# POE_Injector.net
KiCad netlist of a schematic drawn in EAGLE
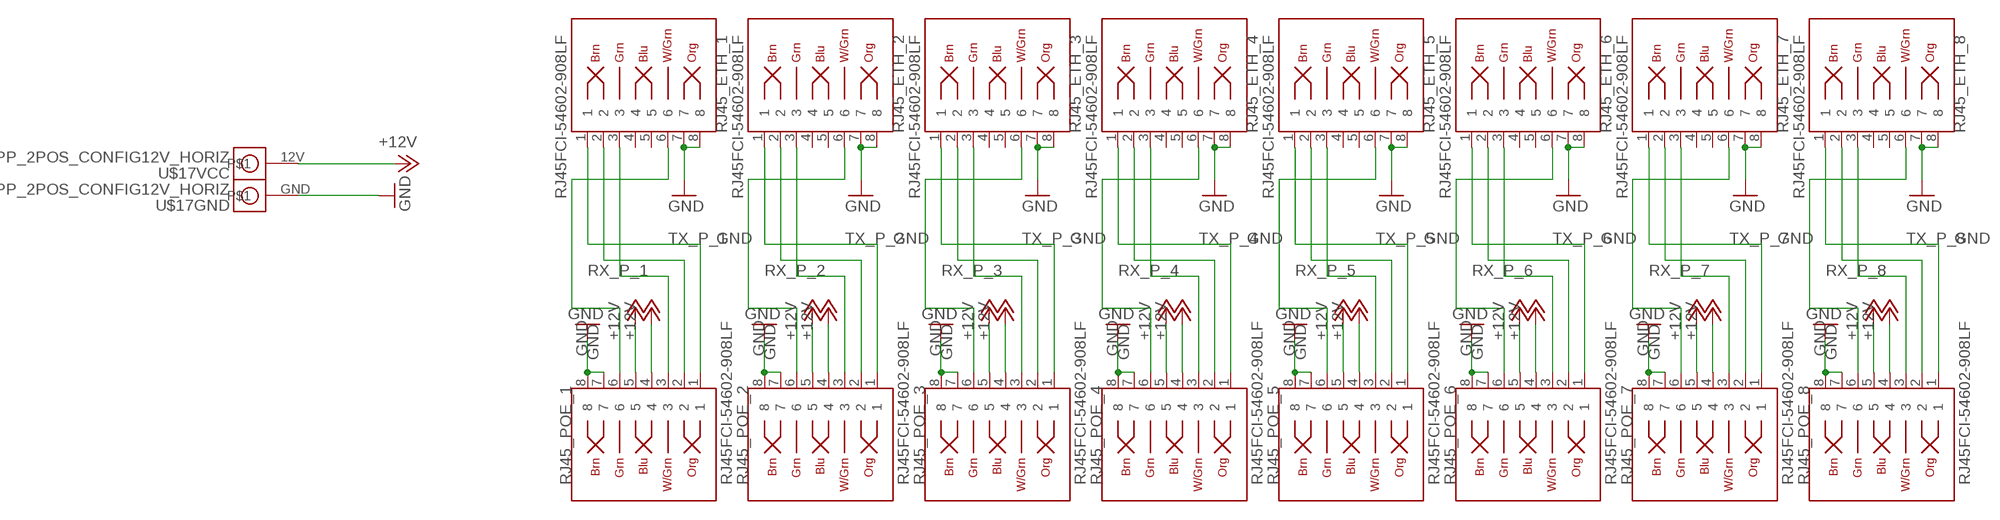
[diagram p0: schematic, sheet 1]

(export (version "E")
  (design (tool "Eeschema 10.0.6"))
  (components
    (comp (ref "RJ45_ETH_1")
      (value "RJ45FCI-54602-908LF")
      (footprint "eagle-import:FCI-54602-908LF")
      (libsource (lib "eagle-import") (part "RJ45FCI-54602-908LF"))
    )
    (comp (ref "RJ45_ETH_2")
      (value "RJ45FCI-54602-908LF")
      (footprint "eagle-import:FCI-54602-908LF")
      (libsource (lib "eagle-import") (part "RJ45FCI-54602-908LF"))
    )
    (comp (ref "RJ45_ETH_3")
      (value "RJ45FCI-54602-908LF")
      (footprint "eagle-import:FCI-54602-908LF")
      (libsource (lib "eagle-import") (part "RJ45FCI-54602-908LF"))
    )
    (comp (ref "RJ45_ETH_4")
      (value "RJ45FCI-54602-908LF")
      (footprint "eagle-import:FCI-54602-908LF")
      (libsource (lib "eagle-import") (part "RJ45FCI-54602-908LF"))
    )
    (comp (ref "RJ45_ETH_5")
      (value "RJ45FCI-54602-908LF")
      (footprint "eagle-import:FCI-54602-908LF")
      (libsource (lib "eagle-import") (part "RJ45FCI-54602-908LF"))
    )
    (comp (ref "RJ45_ETH_6")
      (value "RJ45FCI-54602-908LF")
      (footprint "eagle-import:FCI-54602-908LF")
      (libsource (lib "eagle-import") (part "RJ45FCI-54602-908LF"))
    )
    (comp (ref "RJ45_ETH_7")
      (value "RJ45FCI-54602-908LF")
      (footprint "eagle-import:FCI-54602-908LF")
      (libsource (lib "eagle-import") (part "RJ45FCI-54602-908LF"))
    )
    (comp (ref "RJ45_ETH_8")
      (value "RJ45FCI-54602-908LF")
      (footprint "eagle-import:FCI-54602-908LF")
      (libsource (lib "eagle-import") (part "RJ45FCI-54602-908LF"))
    )
    (comp (ref "RJ45_POE_1")
      (value "RJ45FCI-54602-908LF")
      (footprint "eagle-import:FCI-54602-908LF")
      (libsource (lib "eagle-import") (part "RJ45FCI-54602-908LF"))
    )
    (comp (ref "RJ45_POE_2")
      (value "RJ45FCI-54602-908LF")
      (footprint "eagle-import:FCI-54602-908LF")
      (libsource (lib "eagle-import") (part "RJ45FCI-54602-908LF"))
    )
    (comp (ref "RJ45_POE_3")
      (value "RJ45FCI-54602-908LF")
      (footprint "eagle-import:FCI-54602-908LF")
      (libsource (lib "eagle-import") (part "RJ45FCI-54602-908LF"))
    )
    (comp (ref "RJ45_POE_4")
      (value "RJ45FCI-54602-908LF")
      (footprint "eagle-import:FCI-54602-908LF")
      (libsource (lib "eagle-import") (part "RJ45FCI-54602-908LF"))
    )
    (comp (ref "RJ45_POE_5")
      (value "RJ45FCI-54602-908LF")
      (footprint "eagle-import:FCI-54602-908LF")
      (libsource (lib "eagle-import") (part "RJ45FCI-54602-908LF"))
    )
    (comp (ref "RJ45_POE_6")
      (value "RJ45FCI-54602-908LF")
      (footprint "eagle-import:FCI-54602-908LF")
      (libsource (lib "eagle-import") (part "RJ45FCI-54602-908LF"))
    )
    (comp (ref "RJ45_POE_7")
      (value "RJ45FCI-54602-908LF")
      (footprint "eagle-import:FCI-54602-908LF")
      (libsource (lib "eagle-import") (part "RJ45FCI-54602-908LF"))
    )
    (comp (ref "RJ45_POE_8")
      (value "RJ45FCI-54602-908LF")
      (footprint "eagle-import:FCI-54602-908LF")
      (libsource (lib "eagle-import") (part "RJ45FCI-54602-908LF"))
    )
    (comp (ref "U$17")
      (value "APP_2POS_CONFIG12V_HORIZ")
      (footprint "eagle-import:APP45_12V_HORIZ_CONFIG")
      (libsource (lib "eagle-import") (part "APP_2POS_CONFIG12V_HORIZ"))
    )
  )
  (nets
    (net (code "1") (name "+12V") (class "Default")
      (node (ref "RJ45_POE_1") (pin "4") (pinfunction "4_4") (pintype "bidirectional"))
      (node (ref "RJ45_POE_1") (pin "5") (pinfunction "5_5") (pintype "bidirectional"))
      (node (ref "RJ45_POE_2") (pin "4") (pinfunction "4_4") (pintype "bidirectional"))
      (node (ref "RJ45_POE_2") (pin "5") (pinfunction "5_5") (pintype "bidirectional"))
      (node (ref "RJ45_POE_3") (pin "4") (pinfunction "4_4") (pintype "bidirectional"))
      (node (ref "RJ45_POE_3") (pin "5") (pinfunction "5_5") (pintype "bidirectional"))
      (node (ref "RJ45_POE_4") (pin "4") (pinfunction "4_4") (pintype "bidirectional"))
      (node (ref "RJ45_POE_4") (pin "5") (pinfunction "5_5") (pintype "bidirectional"))
      (node (ref "RJ45_POE_5") (pin "4") (pinfunction "4_4") (pintype "bidirectional"))
      (node (ref "RJ45_POE_5") (pin "5") (pinfunction "5_5") (pintype "bidirectional"))
      (node (ref "RJ45_POE_6") (pin "4") (pinfunction "4_4") (pintype "bidirectional"))
      (node (ref "RJ45_POE_6") (pin "5") (pinfunction "5_5") (pintype "bidirectional"))
      (node (ref "RJ45_POE_7") (pin "4") (pinfunction "4_4") (pintype "bidirectional"))
      (node (ref "RJ45_POE_7") (pin "5") (pinfunction "5_5") (pintype "bidirectional"))
      (node (ref "RJ45_POE_8") (pin "4") (pinfunction "4_4") (pintype "bidirectional"))
      (node (ref "RJ45_POE_8") (pin "5") (pinfunction "5_5") (pintype "bidirectional"))
      (node (ref "U$17") (pin "12V") (pinfunction "P$1_12V") (pintype "bidirectional"))
    )
    (net (code "2") (name "/RX_P_1") (class "Default")
      (node (ref "RJ45_ETH_1") (pin "3") (pinfunction "3_3") (pintype "bidirectional"))
      (node (ref "RJ45_POE_1") (pin "3") (pinfunction "3_3") (pintype "bidirectional"))
    )
    (net (code "3") (name "/RX_P_2") (class "Default")
      (node (ref "RJ45_ETH_2") (pin "3") (pinfunction "3_3") (pintype "bidirectional"))
      (node (ref "RJ45_POE_2") (pin "3") (pinfunction "3_3") (pintype "bidirectional"))
    )
    (net (code "4") (name "/RX_P_3") (class "Default")
      (node (ref "RJ45_ETH_3") (pin "3") (pinfunction "3_3") (pintype "bidirectional"))
      (node (ref "RJ45_POE_3") (pin "3") (pinfunction "3_3") (pintype "bidirectional"))
    )
    (net (code "5") (name "/RX_P_4") (class "Default")
      (node (ref "RJ45_ETH_4") (pin "3") (pinfunction "3_3") (pintype "bidirectional"))
      (node (ref "RJ45_POE_4") (pin "3") (pinfunction "3_3") (pintype "bidirectional"))
    )
    (net (code "6") (name "/RX_P_5") (class "Default")
      (node (ref "RJ45_ETH_5") (pin "3") (pinfunction "3_3") (pintype "bidirectional"))
      (node (ref "RJ45_POE_5") (pin "3") (pinfunction "3_3") (pintype "bidirectional"))
    )
    (net (code "7") (name "/RX_P_6") (class "Default")
      (node (ref "RJ45_ETH_6") (pin "3") (pinfunction "3_3") (pintype "bidirectional"))
      (node (ref "RJ45_POE_6") (pin "3") (pinfunction "3_3") (pintype "bidirectional"))
    )
    (net (code "8") (name "/RX_P_7") (class "Default")
      (node (ref "RJ45_ETH_7") (pin "3") (pinfunction "3_3") (pintype "bidirectional"))
      (node (ref "RJ45_POE_7") (pin "3") (pinfunction "3_3") (pintype "bidirectional"))
    )
    (net (code "9") (name "/RX_P_8") (class "Default")
      (node (ref "RJ45_ETH_8") (pin "3") (pinfunction "3_3") (pintype "bidirectional"))
      (node (ref "RJ45_POE_8") (pin "3") (pinfunction "3_3") (pintype "bidirectional"))
    )
    (net (code "10") (name "/TX_P_1") (class "Default")
      (node (ref "RJ45_ETH_1") (pin "1") (pinfunction "1_1") (pintype "bidirectional"))
      (node (ref "RJ45_POE_1") (pin "1") (pinfunction "1_1") (pintype "bidirectional"))
    )
    (net (code "11") (name "/TX_P_2") (class "Default")
      (node (ref "RJ45_ETH_2") (pin "1") (pinfunction "1_1") (pintype "bidirectional"))
      (node (ref "RJ45_POE_2") (pin "1") (pinfunction "1_1") (pintype "bidirectional"))
    )
    (net (code "12") (name "/TX_P_3") (class "Default")
      (node (ref "RJ45_ETH_3") (pin "1") (pinfunction "1_1") (pintype "bidirectional"))
      (node (ref "RJ45_POE_3") (pin "1") (pinfunction "1_1") (pintype "bidirectional"))
    )
    (net (code "13") (name "/TX_P_4") (class "Default")
      (node (ref "RJ45_ETH_4") (pin "1") (pinfunction "1_1") (pintype "bidirectional"))
      (node (ref "RJ45_POE_4") (pin "1") (pinfunction "1_1") (pintype "bidirectional"))
    )
    (net (code "14") (name "/TX_P_5") (class "Default")
      (node (ref "RJ45_ETH_5") (pin "1") (pinfunction "1_1") (pintype "bidirectional"))
      (node (ref "RJ45_POE_5") (pin "1") (pinfunction "1_1") (pintype "bidirectional"))
    )
    (net (code "15") (name "/TX_P_6") (class "Default")
      (node (ref "RJ45_ETH_6") (pin "1") (pinfunction "1_1") (pintype "bidirectional"))
      (node (ref "RJ45_POE_6") (pin "1") (pinfunction "1_1") (pintype "bidirectional"))
    )
    (net (code "16") (name "/TX_P_7") (class "Default")
      (node (ref "RJ45_ETH_7") (pin "1") (pinfunction "1_1") (pintype "bidirectional"))
      (node (ref "RJ45_POE_7") (pin "1") (pinfunction "1_1") (pintype "bidirectional"))
    )
    (net (code "17") (name "/TX_P_8") (class "Default")
      (node (ref "RJ45_ETH_8") (pin "1") (pinfunction "1_1") (pintype "bidirectional"))
      (node (ref "RJ45_POE_8") (pin "1") (pinfunction "1_1") (pintype "bidirectional"))
    )
    (net (code "18") (name "GND") (class "Default")
      (node (ref "RJ45_ETH_1") (pin "7") (pinfunction "7_7") (pintype "bidirectional"))
      (node (ref "RJ45_ETH_1") (pin "8") (pinfunction "8_8") (pintype "bidirectional"))
      (node (ref "RJ45_ETH_2") (pin "7") (pinfunction "7_7") (pintype "bidirectional"))
      (node (ref "RJ45_ETH_2") (pin "8") (pinfunction "8_8") (pintype "bidirectional"))
      (node (ref "RJ45_ETH_3") (pin "7") (pinfunction "7_7") (pintype "bidirectional"))
      (node (ref "RJ45_ETH_3") (pin "8") (pinfunction "8_8") (pintype "bidirectional"))
      (node (ref "RJ45_ETH_4") (pin "7") (pinfunction "7_7") (pintype "bidirectional"))
      (node (ref "RJ45_ETH_4") (pin "8") (pinfunction "8_8") (pintype "bidirectional"))
      (node (ref "RJ45_ETH_5") (pin "7") (pinfunction "7_7") (pintype "bidirectional"))
      (node (ref "RJ45_ETH_5") (pin "8") (pinfunction "8_8") (pintype "bidirectional"))
      (node (ref "RJ45_ETH_6") (pin "7") (pinfunction "7_7") (pintype "bidirectional"))
      (node (ref "RJ45_ETH_6") (pin "8") (pinfunction "8_8") (pintype "bidirectional"))
      (node (ref "RJ45_ETH_7") (pin "7") (pinfunction "7_7") (pintype "bidirectional"))
      (node (ref "RJ45_ETH_7") (pin "8") (pinfunction "8_8") (pintype "bidirectional"))
      (node (ref "RJ45_ETH_8") (pin "7") (pinfunction "7_7") (pintype "bidirectional"))
      (node (ref "RJ45_ETH_8") (pin "8") (pinfunction "8_8") (pintype "bidirectional"))
      (node (ref "RJ45_POE_1") (pin "7") (pinfunction "7_7") (pintype "bidirectional"))
      (node (ref "RJ45_POE_1") (pin "8") (pinfunction "8_8") (pintype "bidirectional"))
      (node (ref "RJ45_POE_2") (pin "7") (pinfunction "7_7") (pintype "bidirectional"))
      (node (ref "RJ45_POE_2") (pin "8") (pinfunction "8_8") (pintype "bidirectional"))
      (node (ref "RJ45_POE_3") (pin "7") (pinfunction "7_7") (pintype "bidirectional"))
      (node (ref "RJ45_POE_3") (pin "8") (pinfunction "8_8") (pintype "bidirectional"))
      (node (ref "RJ45_POE_4") (pin "7") (pinfunction "7_7") (pintype "bidirectional"))
      (node (ref "RJ45_POE_4") (pin "8") (pinfunction "8_8") (pintype "bidirectional"))
      (node (ref "RJ45_POE_5") (pin "7") (pinfunction "7_7") (pintype "bidirectional"))
      (node (ref "RJ45_POE_5") (pin "8") (pinfunction "8_8") (pintype "bidirectional"))
      (node (ref "RJ45_POE_6") (pin "7") (pinfunction "7_7") (pintype "bidirectional"))
      (node (ref "RJ45_POE_6") (pin "8") (pinfunction "8_8") (pintype "bidirectional"))
      (node (ref "RJ45_POE_7") (pin "7") (pinfunction "7_7") (pintype "bidirectional"))
      (node (ref "RJ45_POE_7") (pin "8") (pinfunction "8_8") (pintype "bidirectional"))
      (node (ref "RJ45_POE_8") (pin "7") (pinfunction "7_7") (pintype "bidirectional"))
      (node (ref "RJ45_POE_8") (pin "8") (pinfunction "8_8") (pintype "bidirectional"))
      (node (ref "U$17") (pin "GND") (pinfunction "P$1_GND") (pintype "bidirectional"))
    )
    (net (code "19") (name "Net-(RJ45_ETH_1-Pad2)") (class "Default")
      (node (ref "RJ45_ETH_1") (pin "2") (pinfunction "2_2") (pintype "bidirectional"))
      (node (ref "RJ45_POE_1") (pin "2") (pinfunction "2_2") (pintype "bidirectional"))
    )
    (net (code "20") (name "Net-(RJ45_ETH_1-Pad6)") (class "Default")
      (node (ref "RJ45_ETH_1") (pin "6") (pinfunction "6_6") (pintype "bidirectional"))
      (node (ref "RJ45_POE_1") (pin "6") (pinfunction "6_6") (pintype "bidirectional"))
    )
    (net (code "21") (name "Net-(RJ45_ETH_2-Pad2)") (class "Default")
      (node (ref "RJ45_ETH_2") (pin "2") (pinfunction "2_2") (pintype "bidirectional"))
      (node (ref "RJ45_POE_2") (pin "2") (pinfunction "2_2") (pintype "bidirectional"))
    )
    (net (code "22") (name "Net-(RJ45_ETH_2-Pad6)") (class "Default")
      (node (ref "RJ45_ETH_2") (pin "6") (pinfunction "6_6") (pintype "bidirectional"))
      (node (ref "RJ45_POE_2") (pin "6") (pinfunction "6_6") (pintype "bidirectional"))
    )
    (net (code "23") (name "Net-(RJ45_ETH_3-Pad2)") (class "Default")
      (node (ref "RJ45_ETH_3") (pin "2") (pinfunction "2_2") (pintype "bidirectional"))
      (node (ref "RJ45_POE_3") (pin "2") (pinfunction "2_2") (pintype "bidirectional"))
    )
    (net (code "24") (name "Net-(RJ45_ETH_3-Pad6)") (class "Default")
      (node (ref "RJ45_ETH_3") (pin "6") (pinfunction "6_6") (pintype "bidirectional"))
      (node (ref "RJ45_POE_3") (pin "6") (pinfunction "6_6") (pintype "bidirectional"))
    )
    (net (code "25") (name "Net-(RJ45_ETH_4-Pad2)") (class "Default")
      (node (ref "RJ45_ETH_4") (pin "2") (pinfunction "2_2") (pintype "bidirectional"))
      (node (ref "RJ45_POE_4") (pin "2") (pinfunction "2_2") (pintype "bidirectional"))
    )
    (net (code "26") (name "Net-(RJ45_ETH_4-Pad6)") (class "Default")
      (node (ref "RJ45_ETH_4") (pin "6") (pinfunction "6_6") (pintype "bidirectional"))
      (node (ref "RJ45_POE_4") (pin "6") (pinfunction "6_6") (pintype "bidirectional"))
    )
    (net (code "27") (name "Net-(RJ45_ETH_5-Pad2)") (class "Default")
      (node (ref "RJ45_ETH_5") (pin "2") (pinfunction "2_2") (pintype "bidirectional"))
      (node (ref "RJ45_POE_5") (pin "2") (pinfunction "2_2") (pintype "bidirectional"))
    )
    (net (code "28") (name "Net-(RJ45_ETH_5-Pad6)") (class "Default")
      (node (ref "RJ45_ETH_5") (pin "6") (pinfunction "6_6") (pintype "bidirectional"))
      (node (ref "RJ45_POE_5") (pin "6") (pinfunction "6_6") (pintype "bidirectional"))
    )
    (net (code "29") (name "Net-(RJ45_ETH_6-Pad2)") (class "Default")
      (node (ref "RJ45_ETH_6") (pin "2") (pinfunction "2_2") (pintype "bidirectional"))
      (node (ref "RJ45_POE_6") (pin "2") (pinfunction "2_2") (pintype "bidirectional"))
    )
    (net (code "30") (name "Net-(RJ45_ETH_6-Pad6)") (class "Default")
      (node (ref "RJ45_ETH_6") (pin "6") (pinfunction "6_6") (pintype "bidirectional"))
      (node (ref "RJ45_POE_6") (pin "6") (pinfunction "6_6") (pintype "bidirectional"))
    )
    (net (code "31") (name "Net-(RJ45_ETH_7-Pad2)") (class "Default")
      (node (ref "RJ45_ETH_7") (pin "2") (pinfunction "2_2") (pintype "bidirectional"))
      (node (ref "RJ45_POE_7") (pin "2") (pinfunction "2_2") (pintype "bidirectional"))
    )
    (net (code "32") (name "Net-(RJ45_ETH_7-Pad6)") (class "Default")
      (node (ref "RJ45_ETH_7") (pin "6") (pinfunction "6_6") (pintype "bidirectional"))
      (node (ref "RJ45_POE_7") (pin "6") (pinfunction "6_6") (pintype "bidirectional"))
    )
    (net (code "33") (name "Net-(RJ45_ETH_8-Pad2)") (class "Default")
      (node (ref "RJ45_ETH_8") (pin "2") (pinfunction "2_2") (pintype "bidirectional"))
      (node (ref "RJ45_POE_8") (pin "2") (pinfunction "2_2") (pintype "bidirectional"))
    )
    (net (code "34") (name "Net-(RJ45_ETH_8-Pad6)") (class "Default")
      (node (ref "RJ45_ETH_8") (pin "6") (pinfunction "6_6") (pintype "bidirectional"))
      (node (ref "RJ45_POE_8") (pin "6") (pinfunction "6_6") (pintype "bidirectional"))
    )
    (net (code "35") (name "unconnected-(RJ45_ETH_1-Pad4)") (class "Default")
      (node (ref "RJ45_ETH_1") (pin "4") (pinfunction "4_4") (pintype "bidirectional"))
    )
    (net (code "36") (name "unconnected-(RJ45_ETH_1-Pad5)") (class "Default")
      (node (ref "RJ45_ETH_1") (pin "5") (pinfunction "5_5") (pintype "bidirectional"))
    )
    (net (code "37") (name "unconnected-(RJ45_ETH_2-Pad4)") (class "Default")
      (node (ref "RJ45_ETH_2") (pin "4") (pinfunction "4_4") (pintype "bidirectional"))
    )
    (net (code "38") (name "unconnected-(RJ45_ETH_2-Pad5)") (class "Default")
      (node (ref "RJ45_ETH_2") (pin "5") (pinfunction "5_5") (pintype "bidirectional"))
    )
    (net (code "39") (name "unconnected-(RJ45_ETH_3-Pad4)") (class "Default")
      (node (ref "RJ45_ETH_3") (pin "4") (pinfunction "4_4") (pintype "bidirectional"))
    )
    (net (code "40") (name "unconnected-(RJ45_ETH_3-Pad5)") (class "Default")
      (node (ref "RJ45_ETH_3") (pin "5") (pinfunction "5_5") (pintype "bidirectional"))
    )
    (net (code "41") (name "unconnected-(RJ45_ETH_4-Pad4)") (class "Default")
      (node (ref "RJ45_ETH_4") (pin "4") (pinfunction "4_4") (pintype "bidirectional"))
    )
    (net (code "42") (name "unconnected-(RJ45_ETH_4-Pad5)") (class "Default")
      (node (ref "RJ45_ETH_4") (pin "5") (pinfunction "5_5") (pintype "bidirectional"))
    )
    (net (code "43") (name "unconnected-(RJ45_ETH_5-Pad4)") (class "Default")
      (node (ref "RJ45_ETH_5") (pin "4") (pinfunction "4_4") (pintype "bidirectional"))
    )
    (net (code "44") (name "unconnected-(RJ45_ETH_5-Pad5)") (class "Default")
      (node (ref "RJ45_ETH_5") (pin "5") (pinfunction "5_5") (pintype "bidirectional"))
    )
    (net (code "45") (name "unconnected-(RJ45_ETH_6-Pad4)") (class "Default")
      (node (ref "RJ45_ETH_6") (pin "4") (pinfunction "4_4") (pintype "bidirectional"))
    )
    (net (code "46") (name "unconnected-(RJ45_ETH_6-Pad5)") (class "Default")
      (node (ref "RJ45_ETH_6") (pin "5") (pinfunction "5_5") (pintype "bidirectional"))
    )
    (net (code "47") (name "unconnected-(RJ45_ETH_7-Pad4)") (class "Default")
      (node (ref "RJ45_ETH_7") (pin "4") (pinfunction "4_4") (pintype "bidirectional"))
    )
    (net (code "48") (name "unconnected-(RJ45_ETH_7-Pad5)") (class "Default")
      (node (ref "RJ45_ETH_7") (pin "5") (pinfunction "5_5") (pintype "bidirectional"))
    )
    (net (code "49") (name "unconnected-(RJ45_ETH_8-Pad4)") (class "Default")
      (node (ref "RJ45_ETH_8") (pin "4") (pinfunction "4_4") (pintype "bidirectional"))
    )
    (net (code "50") (name "unconnected-(RJ45_ETH_8-Pad5)") (class "Default")
      (node (ref "RJ45_ETH_8") (pin "5") (pinfunction "5_5") (pintype "bidirectional"))
    )
  )
)
